# Power_Sheet.net
KiCad netlist of a schematic drawn in Altium Designer
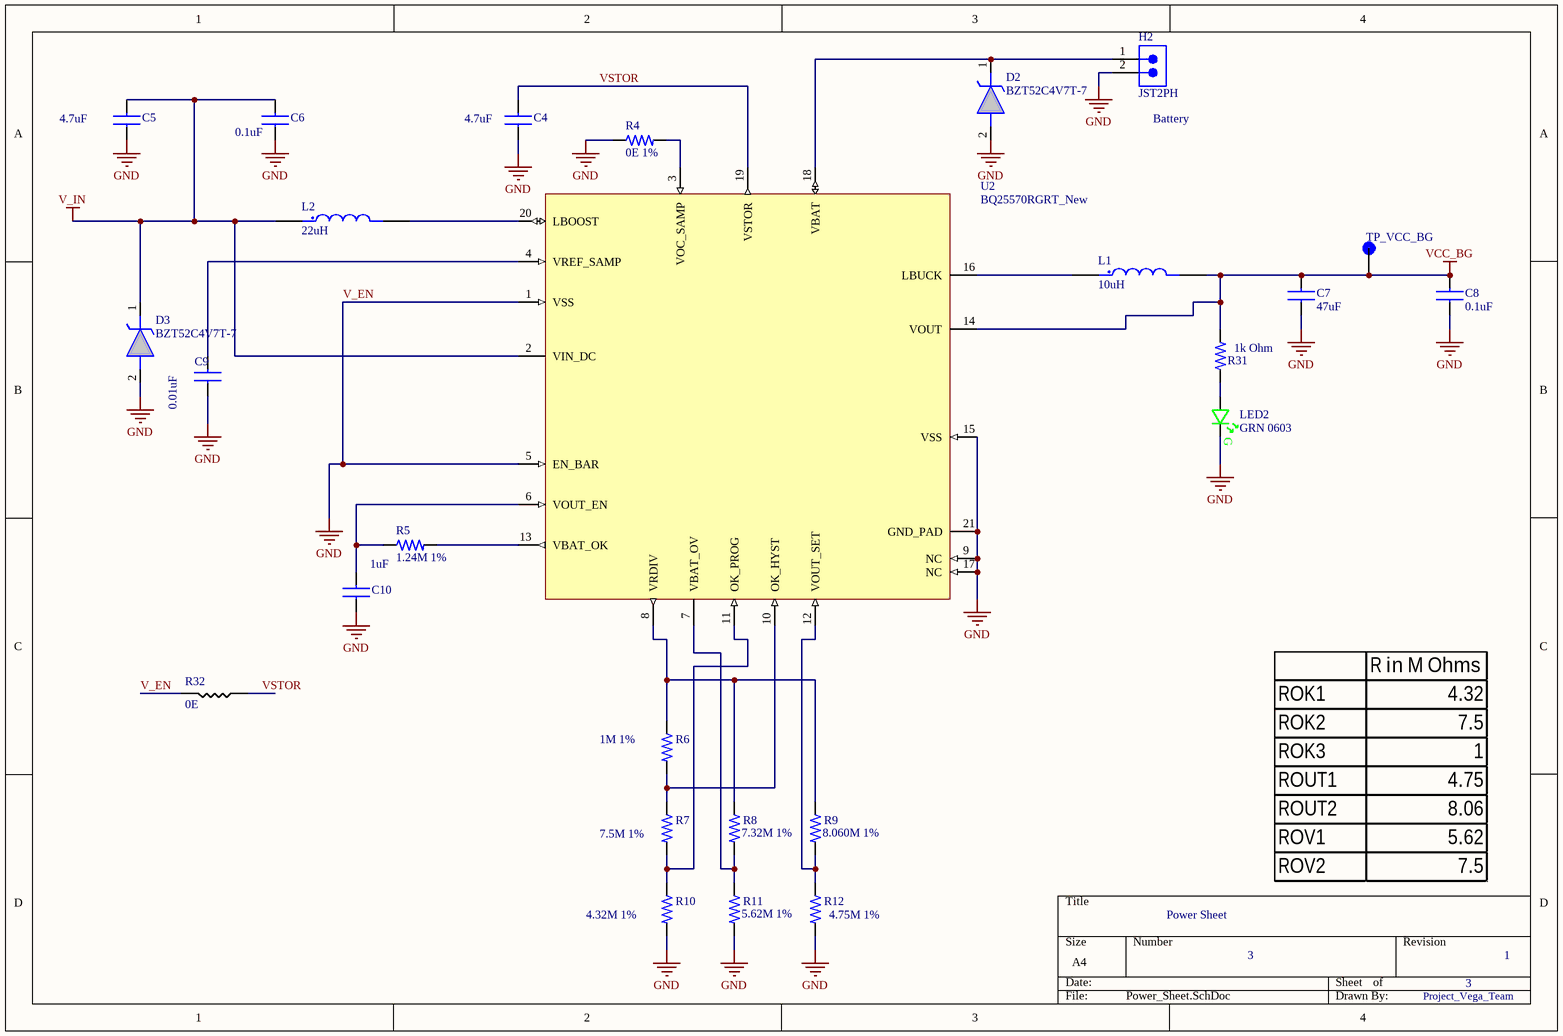
[diagram p0: Power_Sheet.SchDoc]

(export (version "E")
  (design (tool "Eeschema 10.0.6"))
  (components
    (comp (ref "C4")
      (value "4.7uF")
      (footprint "CAP_0603_1MM")
      (description "CAP CER 22UF 10V X5R 0603")
      (fields
        (field (name "MANUFACTURER") "Murata")
        (field (name "MANUFACTURER PART NUMBER") "GRM188R61A226ME15D")
      )
      (libsource (lib "LPEDT_Parts") (part "GRM188R61A226ME15D"))
    )
    (comp (ref "C5")
      (value "4.7uF")
      (footprint "CAP_0603_1MM")
      (description "CAP CER 22UF 10V X5R 0603")
      (fields
        (field (name "MANUFACTURER") "Murata")
        (field (name "MANUFACTURER PART NUMBER") "GRM188R61A226ME15D")
      )
      (libsource (lib "LPEDT_Parts") (part "GRM188R61A226ME15D"))
    )
    (comp (ref "C6")
      (value "0.1uF")
      (footprint "CAP_0603_1MM")
      (description "CAP CER 22UF 10V X5R 0603")
      (fields
        (field (name "MANUFACTURER") "Murata")
        (field (name "MANUFACTURER PART NUMBER") "GRM188R61A226ME15D")
      )
      (libsource (lib "LPEDT_Parts") (part "GRM188R61A226ME15D"))
    )
    (comp (ref "C7")
      (value "47uF")
      (footprint "CAP_0603_1MM")
      (description "CAP CER 22UF 10V X5R 0603")
      (fields
        (field (name "MANUFACTURER") "Murata")
        (field (name "MANUFACTURER PART NUMBER") "GRM188R61A226ME15D")
      )
      (libsource (lib "LPEDT_Parts") (part "GRM188R61A226ME15D"))
    )
    (comp (ref "C8")
      (value "0.1uF")
      (footprint "CAP_0603_1MM")
      (description "CAP CER 22UF 10V X5R 0603")
      (fields
        (field (name "MANUFACTURER") "Murata")
        (field (name "MANUFACTURER PART NUMBER") "GRM188R61A226ME15D")
      )
      (libsource (lib "LPEDT_Parts") (part "GRM188R61A226ME15D"))
    )
    (comp (ref "C9")
      (value "0.01uF")
      (footprint "CAP_0603_1MM")
      (description "CAP CER 22UF 10V X5R 0603")
      (fields
        (field (name "MANUFACTURER") "Murata")
        (field (name "MANUFACTURER PART NUMBER") "GRM188R61A226ME15D")
      )
      (libsource (lib "LPEDT_Parts") (part "GRM188R61A226ME15D"))
    )
    (comp (ref "C10")
      (value "1uF")
      (footprint "CAP_0603_1MM")
      (description "CAP CER 22UF 10V X5R 0603")
      (fields
        (field (name "MANUFACTURER") "Murata")
        (field (name "MANUFACTURER PART NUMBER") "GRM188R61A226ME15D")
      )
      (libsource (lib "LPEDT_Parts") (part "GRM188R61A226ME15D"))
    )
    (comp (ref "D2")
      (value "BZT52C4V7T-7")
      (footprint "SOD3715X135N")
      (description "Diode Zener Single 4.7V 6% 300mW 2-Pin SOD-523 T/R")
      (fields (field (name "MOUSER PART NUMBER") "621-BZT52C4V7T-7") (field (name "MANUFACTURER") "Diodes"))
      (libsource (lib "Project_Vega") (part "BZT52C4V7T-7"))
    )
    (comp (ref "D3")
      (value "BZT52C4V7T-7")
      (footprint "SOD3715X135N")
      (description "Diode Zener Single 4.7V 6% 300mW 2-Pin SOD-523 T/R")
      (fields (field (name "MOUSER PART NUMBER") "621-BZT52C4V7T-7") (field (name "MANUFACTURER") "Diodes"))
      (libsource (lib "Project_Vega") (part "BZT52C4V7T-7"))
    )
    (comp (ref "H2")
      (value "JST2PH")
      (footprint "JST_B2B-PH-K-S(LF)(SN)")
      (description "Connector Header Through Hole 2 position 0.079\" (2.00mm)")
      (fields (field (name "MANUFACTURER") "JST") (field (name "MANUFACTURER PART NUMBER") "B2B-PH-K-S"))
      (libsource (lib "Connectors") (part "JST2PH"))
    )
    (comp (ref "L1")
      (value "10uH")
      (footprint "IND_LPS4018-103MRB")
      (description "Power inductor, shielded, 20/30% tol, SMT, RoHS, lead-free, halogen-free")
      (fields (field (name "MF") "Coilcraft") (field (name "MP") "LPS4018-103MRB"))
      (libsource (lib "Project_Vega") (part "LPS4018-103MRB"))
    )
    (comp (ref "L2")
      (value "22uH")
      (footprint "IND_LPS4018-223MRC")
      (description "22 µH Shielded Drum Core Inductor 650 mA 360mOhm Max Nonstandard")
      (fields (field (name "MF") "Coilcraft") (field (name "MP") "LPS4018-223MRC"))
      (libsource (lib "LPS4018-223MRC") (part "LPS4018-223MRC"))
    )
    (comp (ref "LED2")
      (value "GRN 0603")
      (footprint "LED_0603_GRN_WL-SMCW")
      (description "430mcd Colorless transparence 520nm Emerald 140° LED0603 Light Emitting Diodes (LED) ROHS")
      (fields
        (field (name "MANUFACTURER") "Wurth Electronics")
        (field (name "MANUFACTURER PART NUMBER") "150060GS75000")
      )
      (libsource (lib "Project_Vega") (part "LED_green"))
    )
    (comp (ref "R4")
      (value "0E 1%")
      (footprint "RES_0603_1608X06")
      (description "SMD Chip Resistor, 316 kOhm, ± 1%, 100 mW, 0603 [1608 Metric], Thick Film, General Purpose")
      (fields
        (field (name "MANUFACTURER") "Yageo")
        (field (name "MANUFACTURER PART NUMBER") "RC0603FR-07316KL")
      )
      (libsource (lib "LPEDT_Parts") (part "RC0603FR-07316KL"))
    )
    (comp (ref "R5")
      (value "1.24M 1%")
      (footprint "RES_0603_1608X06")
      (description "SMD Chip Resistor, 316 kOhm, ± 1%, 100 mW, 0603 [1608 Metric], Thick Film, General Purpose")
      (fields
        (field (name "MANUFACTURER") "Yageo")
        (field (name "MANUFACTURER PART NUMBER") "RC0603FR-07316KL")
      )
      (libsource (lib "LPEDT_Parts") (part "RC0603FR-07316KL"))
    )
    (comp (ref "R6")
      (value "1M 1%")
      (footprint "RES_0603_1608X06")
      (description "SMD Chip Resistor, 316 kOhm, ± 1%, 100 mW, 0603 [1608 Metric], Thick Film, General Purpose")
      (fields
        (field (name "MANUFACTURER") "Yageo")
        (field (name "MANUFACTURER PART NUMBER") "RC0603FR-07316KL")
      )
      (libsource (lib "LPEDT_Parts") (part "RC0603FR-07316KL"))
    )
    (comp (ref "R7")
      (value "7.5M 1%")
      (footprint "RES_0603_1608X06")
      (description "SMD Chip Resistor, 316 kOhm, ± 1%, 100 mW, 0603 [1608 Metric], Thick Film, General Purpose")
      (fields
        (field (name "MANUFACTURER") "Yageo")
        (field (name "MANUFACTURER PART NUMBER") "RC0603FR-07316KL")
      )
      (libsource (lib "LPEDT_Parts") (part "RC0603FR-07316KL"))
    )
    (comp (ref "R8")
      (value "7.32M 1%")
      (footprint "RES_0603_1608X06")
      (description "SMD Chip Resistor, 316 kOhm, ± 1%, 100 mW, 0603 [1608 Metric], Thick Film, General Purpose")
      (fields
        (field (name "MANUFACTURER") "Yageo")
        (field (name "MANUFACTURER PART NUMBER") "RC0603FR-07316KL")
      )
      (libsource (lib "LPEDT_Parts") (part "RC0603FR-07316KL"))
    )
    (comp (ref "R9")
      (value "8.060M 1%")
      (footprint "RES_0603_1608X06")
      (description "SMD Chip Resistor, 316 kOhm, ± 1%, 100 mW, 0603 [1608 Metric], Thick Film, General Purpose")
      (fields
        (field (name "MANUFACTURER") "Yageo")
        (field (name "MANUFACTURER PART NUMBER") "RC0603FR-07316KL")
      )
      (libsource (lib "LPEDT_Parts") (part "RC0603FR-07316KL"))
    )
    (comp (ref "R10")
      (value "4.32M 1%")
      (footprint "RES_0603_1608X06")
      (description "SMD Chip Resistor, 316 kOhm, ± 1%, 100 mW, 0603 [1608 Metric], Thick Film, General Purpose")
      (fields
        (field (name "MANUFACTURER") "Yageo")
        (field (name "MANUFACTURER PART NUMBER") "RC0603FR-07316KL")
      )
      (libsource (lib "LPEDT_Parts") (part "RC0603FR-07316KL"))
    )
    (comp (ref "R11")
      (value "5.62M 1%")
      (footprint "RES_0603_1608X06")
      (description "SMD Chip Resistor, 316 kOhm, ± 1%, 100 mW, 0603 [1608 Metric], Thick Film, General Purpose")
      (fields
        (field (name "MANUFACTURER") "Yageo")
        (field (name "MANUFACTURER PART NUMBER") "RC0603FR-07316KL")
      )
      (libsource (lib "LPEDT_Parts") (part "RC0603FR-07316KL"))
    )
    (comp (ref "R12")
      (value "4.75M 1%")
      (footprint "RES_0603_1608X06")
      (description "SMD Chip Resistor, 316 kOhm, ± 1%, 100 mW, 0603 [1608 Metric], Thick Film, General Purpose")
      (fields
        (field (name "MANUFACTURER") "Yageo")
        (field (name "MANUFACTURER PART NUMBER") "RC0603FR-07316KL")
      )
      (libsource (lib "LPEDT_Parts") (part "RC0603FR-07316KL"))
    )
    (comp (ref "R31")
      (value "1k Ohm")
      (footprint "RES_0603")
      (description "Thick film general purpose resistor 0603")
      (fields (field (name "MP") "RC0603JR-070RL"))
      (libsource (lib "Project_Vega") (part "RES_0603"))
    )
    (comp (ref "R32")
      (value "0E")
      (footprint "1206_Passive_Resitor")
      (description "10 kOhms ±5% 0.25W, 1/4W Chip Resistor 1206 (3216 Metric) Automotive AEC-Q200 Thick Film")
      (fields (field (name "MFR PART #") "RMCF1206FT10K0") (field (name "LCSC PART#") "C17902"))
      (libsource (lib "ECEN5730Lib_2023_05_DS") (part "R_10KOhm_1206"))
    )
    (comp (ref "TP_VCC_BG")
      (value "Test_point")
      (footprint "1")
      (description "SMT Test Point- Mininature-1000 pc Reels")
      (fields (field (name "MP") "5019") (field (name "MF") "Keystone Electronics"))
      (libsource (lib "Project_Vega") (part "Test_point"))
    )
    (comp (ref "U2")
      (value "BQ25570RGRT_New")
      (footprint "QFN50P350X350X100-21N - duplicate")
      (description "Switching Battery Charger Li-Ion/Li-Pol/Supercapacitor 110mA 2.2V to 5.5V 20-Pin VQFN EP T/R")
      (fields
        (field (name "MANUFACTURER") "Texas Instruments")
        (field (name "MANUFACTURER PART NUMBER") "BQ25570RGRT")
      )
      (libsource (lib "Project_Vega") (part "BQ25570RGRT_New"))
    )
  )
  (nets
    (net (code "1") (name "/VSTOR") (class "Default")
      (node (ref "C4") (pin "2") (pinfunction "2_2") (pintype "passive"))
      (node (ref "R32") (pin "1") (pinfunction "1_1") (pintype "passive"))
      (node (ref "U2") (pin "19") (pinfunction "VSTOR_19") (pintype "output"))
    )
    (net (code "2") (name "GND") (class "Default")
      (node (ref "C10") (pin "1") (pinfunction "1_1") (pintype "passive"))
      (node (ref "C4") (pin "1") (pinfunction "1_1") (pintype "passive"))
      (node (ref "C5") (pin "1") (pinfunction "1_1") (pintype "passive"))
      (node (ref "C6") (pin "1") (pinfunction "1_1") (pintype "passive"))
      (node (ref "C7") (pin "1") (pinfunction "1_1") (pintype "passive"))
      (node (ref "C8") (pin "1") (pinfunction "1_1") (pintype "passive"))
      (node (ref "C9") (pin "1") (pinfunction "1_1") (pintype "passive"))
      (node (ref "D2") (pin "2") (pinfunction "A_2") (pintype "passive"))
      (node (ref "D3") (pin "2") (pinfunction "A_2") (pintype "passive"))
      (node (ref "H2") (pin "2") (pinfunction "2_2") (pintype "passive"))
      (node (ref "LED2") (pin "C") (pinfunction "C_C") (pintype "passive"))
      (node (ref "R10") (pin "2") (pinfunction "2_2") (pintype "passive"))
      (node (ref "R11") (pin "2") (pinfunction "2_2") (pintype "passive"))
      (node (ref "R12") (pin "2") (pinfunction "2_2") (pintype "passive"))
      (node (ref "R32") (pin "2") (pinfunction "2_2") (pintype "passive"))
      (node (ref "R4") (pin "1") (pinfunction "1_1") (pintype "passive"))
      (node (ref "U2") (pin "1") (pinfunction "VSS_1") (pintype "input"))
      (node (ref "U2") (pin "15") (pinfunction "VSS_15") (pintype "input"))
      (node (ref "U2") (pin "17") (pinfunction "NC_17") (pintype "input"))
      (node (ref "U2") (pin "21") (pinfunction "GND_PAD_21") (pintype "power_in"))
      (node (ref "U2") (pin "5") (pinfunction "EN_BAR_5") (pintype "input"))
      (node (ref "U2") (pin "9") (pinfunction "NC_9") (pintype "input"))
    )
    (net (code "3") (name "Net-(D2-K)") (class "Default")
      (node (ref "D2") (pin "1") (pinfunction "K_1") (pintype "passive"))
      (node (ref "H2") (pin "1") (pinfunction "1_1") (pintype "passive"))
      (node (ref "U2") (pin "18") (pinfunction "VBAT_18") (pintype "bidirectional"))
    )
    (net (code "4") (name "Net-(LED2-PadA)") (class "Default")
      (node (ref "LED2") (pin "A") (pinfunction "A_A") (pintype "passive"))
      (node (ref "R31") (pin "1") (pinfunction "1_1") (pintype "passive"))
    )
    (net (code "5") (name "Net-(U2-LBOOST)") (class "Default")
      (node (ref "L2") (pin "2") (pinfunction "2_2") (pintype "passive"))
      (node (ref "U2") (pin "20") (pinfunction "LBOOST_20") (pintype "bidirectional"))
    )
    (net (code "6") (name "Net-(U2-LBUCK)") (class "Default")
      (node (ref "L1") (pin "1") (pinfunction "1_1") (pintype "passive"))
      (node (ref "U2") (pin "16") (pinfunction "LBUCK_16") (pintype "power_in"))
    )
    (net (code "7") (name "Net-(U2-OK_HYST)") (class "Default")
      (node (ref "R6") (pin "2") (pinfunction "2_2") (pintype "passive"))
      (node (ref "R7") (pin "1") (pinfunction "1_1") (pintype "passive"))
      (node (ref "U2") (pin "10") (pinfunction "OK_HYST_10") (pintype "input"))
    )
    (net (code "8") (name "Net-(U2-OK_PROG)") (class "Default")
      (node (ref "R10") (pin "1") (pinfunction "1_1") (pintype "passive"))
      (node (ref "R7") (pin "2") (pinfunction "2_2") (pintype "passive"))
      (node (ref "U2") (pin "11") (pinfunction "OK_PROG_11") (pintype "input"))
    )
    (net (code "9") (name "Net-(U2-VBAT_OK)") (class "Default")
      (node (ref "R5") (pin "2") (pinfunction "2_2") (pintype "passive"))
      (node (ref "U2") (pin "13") (pinfunction "VBAT_OK_13") (pintype "output"))
    )
    (net (code "10") (name "Net-(U2-VBAT_OV)") (class "Default")
      (node (ref "R11") (pin "1") (pinfunction "1_1") (pintype "passive"))
      (node (ref "R8") (pin "2") (pinfunction "2_2") (pintype "passive"))
      (node (ref "U2") (pin "7") (pinfunction "VBAT_OV_7") (pintype "power_in"))
    )
    (net (code "11") (name "Net-(U2-VOC_SAMP)") (class "Default")
      (node (ref "R4") (pin "2") (pinfunction "2_2") (pintype "passive"))
      (node (ref "U2") (pin "3") (pinfunction "VOC_SAMP_3") (pintype "input"))
    )
    (net (code "12") (name "Net-(U2-VOUT_EN)") (class "Default")
      (node (ref "C10") (pin "2") (pinfunction "2_2") (pintype "passive"))
      (node (ref "R5") (pin "1") (pinfunction "1_1") (pintype "passive"))
      (node (ref "U2") (pin "6") (pinfunction "VOUT_EN_6") (pintype "input"))
    )
    (net (code "13") (name "Net-(U2-VOUT_SET)") (class "Default")
      (node (ref "R12") (pin "1") (pinfunction "1_1") (pintype "passive"))
      (node (ref "R9") (pin "2") (pinfunction "2_2") (pintype "passive"))
      (node (ref "U2") (pin "12") (pinfunction "VOUT_SET_12") (pintype "input"))
    )
    (net (code "14") (name "Net-(U2-VRDIV)") (class "Default")
      (node (ref "R6") (pin "1") (pinfunction "1_1") (pintype "passive"))
      (node (ref "R8") (pin "1") (pinfunction "1_1") (pintype "passive"))
      (node (ref "R9") (pin "1") (pinfunction "1_1") (pintype "passive"))
      (node (ref "U2") (pin "8") (pinfunction "VRDIV_8") (pintype "output"))
    )
    (net (code "15") (name "Net-(U2-VREF_SAMP)") (class "Default")
      (node (ref "C9") (pin "2") (pinfunction "2_2") (pintype "passive"))
      (node (ref "U2") (pin "4") (pinfunction "VREF_SAMP_4") (pintype "input"))
    )
    (net (code "16") (name "VCC_BG") (class "Default")
      (node (ref "C7") (pin "2") (pinfunction "2_2") (pintype "passive"))
      (node (ref "C8") (pin "2") (pinfunction "2_2") (pintype "passive"))
      (node (ref "L1") (pin "2") (pinfunction "2_2") (pintype "passive"))
      (node (ref "R31") (pin "2") (pinfunction "2_2") (pintype "passive"))
      (node (ref "TP_VCC_BG") (pin "TP") (pinfunction "VCC_BG_TP") (pintype "passive"))
      (node (ref "U2") (pin "14") (pinfunction "VOUT_14") (pintype "power_in"))
    )
    (net (code "17") (name "V_IN") (class "Default")
      (node (ref "C5") (pin "2") (pinfunction "2_2") (pintype "passive"))
      (node (ref "C6") (pin "2") (pinfunction "2_2") (pintype "passive"))
      (node (ref "D3") (pin "1") (pinfunction "K_1") (pintype "passive"))
      (node (ref "L2") (pin "1") (pinfunction "1_1") (pintype "passive"))
      (node (ref "U2") (pin "2") (pinfunction "VIN_DC_2") (pintype "power_in"))
    )
  )
)
